# balancing_protection.net
KiCad netlist of a schematic drawn in Altium Designer
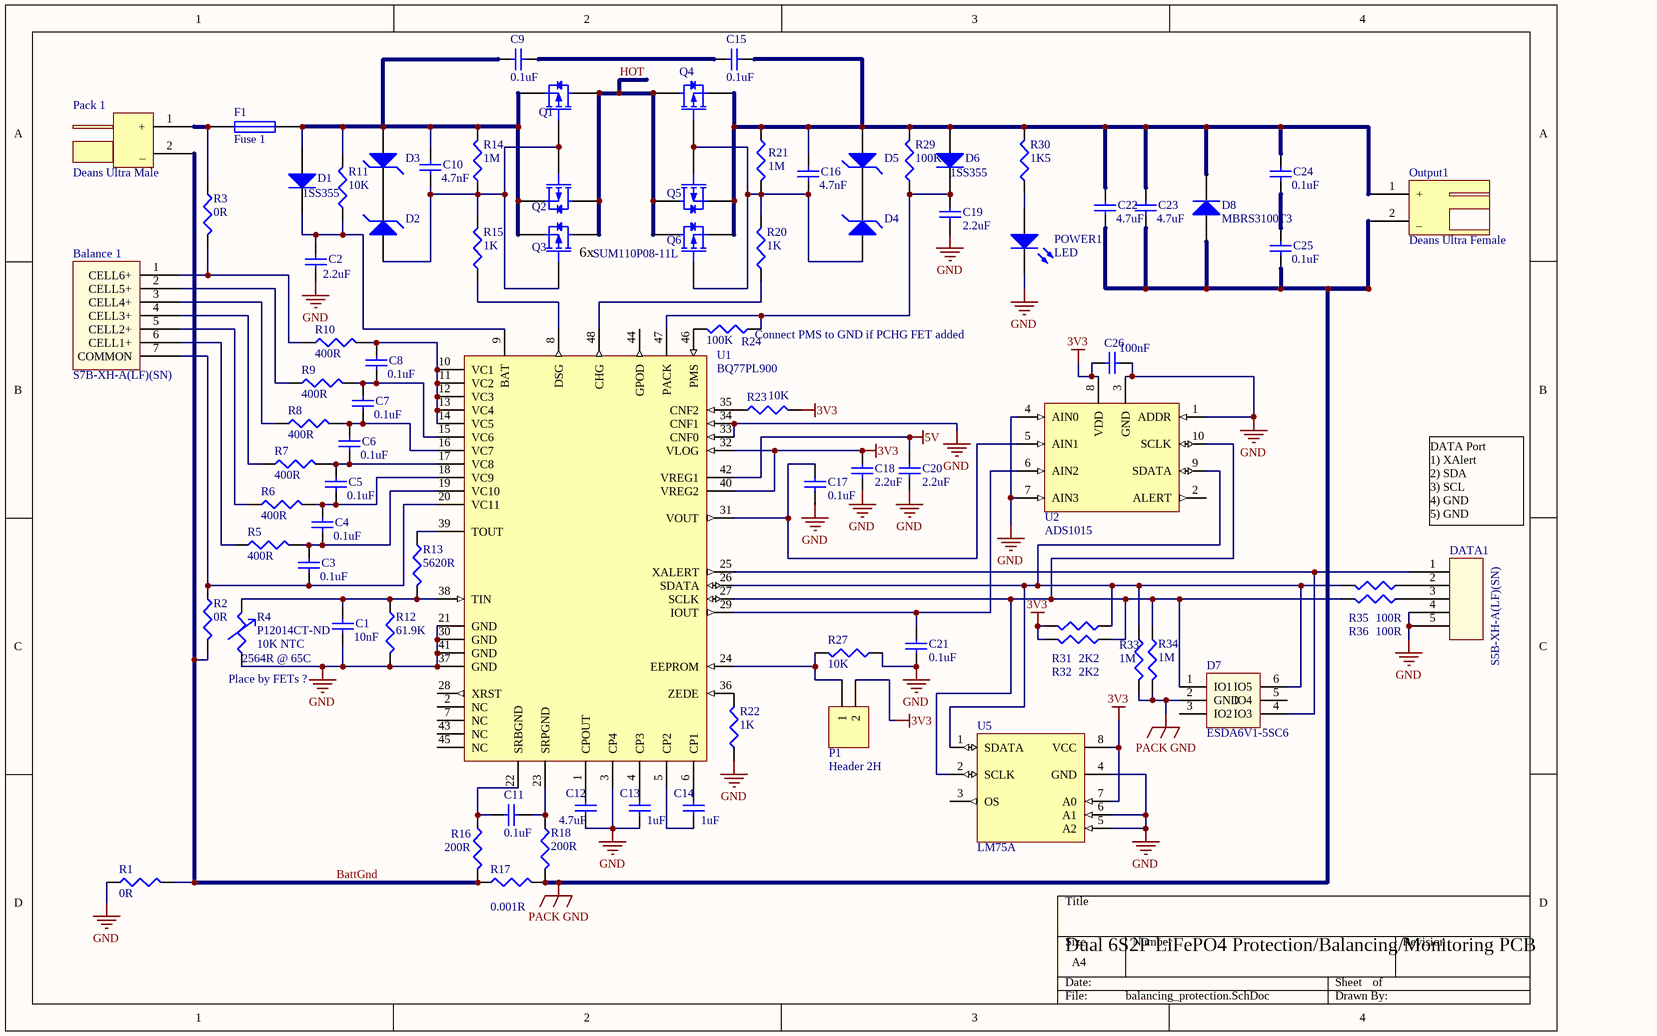
[diagram p0: balancing_protection.SchDoc]

(export (version "E")
  (design (tool "Eeschema 10.0.6"))
  (components
    (comp (ref "Balance 1")
      (value "S7B-XH-A(LF)(SN)")
      (footprint "XH_BALANCE_CONN")
      (description "Balancing Connector 455-2240-ND")
      (libsource (lib "parts") (part "S7B-XH-A(LF)(SN)"))
    )
    (comp (ref "C1")
      (value "10nF")
      (footprint "0603 - Hugo copy")
      (description "Capacitor (Semiconductor SIM Model)")
      (fields (field (name "Comment") "Cap Semi") (field (name "PUBLISHER") "Altium Limited"))
      (libsource (lib "Miscellaneous Devices") (part "Cap Semi"))
    )
    (comp (ref "C2")
      (value "2.2uF")
      (footprint "CAPC1206X06N")
      (description "TANTAMOUNT® 293D series tantalum 1206 cap")
      (fields (field (name "Comment") "718-1113-1-ND") (field (name "PUBLISHER") "Altium Limited"))
      (libsource (lib "parts") (part "TantCap1206"))
    )
    (comp (ref "C3")
      (value "0.1uF")
      (footprint "0603 - Hugo copy")
      (description "Capacitor (Semiconductor SIM Model)")
      (fields (field (name "Comment") "Cap Semi") (field (name "PUBLISHER") "Altium Limited"))
      (libsource (lib "Miscellaneous Devices") (part "Cap Semi"))
    )
    (comp (ref "C4")
      (value "0.1uF")
      (footprint "0603 - Hugo copy")
      (description "Capacitor (Semiconductor SIM Model)")
      (fields (field (name "Comment") "Cap Semi") (field (name "PUBLISHER") "Altium Limited"))
      (libsource (lib "Miscellaneous Devices") (part "Cap Semi"))
    )
    (comp (ref "C5")
      (value "0.1uF")
      (footprint "0603 - Hugo copy")
      (description "Capacitor (Semiconductor SIM Model)")
      (fields (field (name "Comment") "Cap Semi") (field (name "PUBLISHER") "Altium Limited"))
      (libsource (lib "Miscellaneous Devices") (part "Cap Semi"))
    )
    (comp (ref "C6")
      (value "0.1uF")
      (footprint "0603 - Hugo copy")
      (description "Capacitor (Semiconductor SIM Model)")
      (fields (field (name "Comment") "Cap Semi") (field (name "PUBLISHER") "Altium Limited"))
      (libsource (lib "Miscellaneous Devices") (part "Cap Semi"))
    )
    (comp (ref "C7")
      (value "0.1uF")
      (footprint "0603 - Hugo copy")
      (description "Capacitor (Semiconductor SIM Model)")
      (fields (field (name "Comment") "Cap Semi") (field (name "PUBLISHER") "Altium Limited"))
      (libsource (lib "Miscellaneous Devices") (part "Cap Semi"))
    )
    (comp (ref "C8")
      (value "0.1uF")
      (footprint "0603 - Hugo copy")
      (description "Capacitor (Semiconductor SIM Model)")
      (fields (field (name "Comment") "Cap Semi") (field (name "PUBLISHER") "Altium Limited"))
      (libsource (lib "Miscellaneous Devices") (part "Cap Semi"))
    )
    (comp (ref "C9")
      (value "0.1uF")
      (footprint "0603 - Hugo copy")
      (description "Capacitor (Semiconductor SIM Model)")
      (fields (field (name "Comment") "Cap Semi") (field (name "PUBLISHER") "Altium Limited"))
      (libsource (lib "Miscellaneous Devices") (part "Cap Semi"))
    )
    (comp (ref "C10")
      (value "4.7nF")
      (footprint "0603 - Hugo copy")
      (description "Capacitor (Semiconductor SIM Model)")
      (fields (field (name "Comment") "Cap Semi") (field (name "PUBLISHER") "Altium Limited"))
      (libsource (lib "Miscellaneous Devices") (part "Cap Semi"))
    )
    (comp (ref "C11")
      (value "0.1uF")
      (footprint "0603 - Hugo copy")
      (description "Capacitor (Semiconductor SIM Model)")
      (fields (field (name "Comment") "Cap Semi") (field (name "PUBLISHER") "Altium Limited"))
      (libsource (lib "Miscellaneous Devices") (part "Cap Semi"))
    )
    (comp (ref "C12")
      (value "4.7uF")
      (footprint "CAPC1210X10N")
      (description "TANTAMOUNT® 293D series tantalum 1206 cap")
      (fields (field (name "Comment") "718-1113-1-ND") (field (name "PUBLISHER") "Altium Limited"))
      (libsource (lib "parts") (part "TantCap1206"))
    )
    (comp (ref "C13")
      (value "1uF")
      (footprint "CAPC1206X06N")
      (description "TANTAMOUNT® 293D series tantalum 1206 cap")
      (fields (field (name "Comment") "718-1113-1-ND") (field (name "PUBLISHER") "Altium Limited"))
      (libsource (lib "parts") (part "TantCap1206"))
    )
    (comp (ref "C14")
      (value "1uF")
      (footprint "CAPC1206X06N")
      (description "TANTAMOUNT® 293D series tantalum 1206 cap")
      (fields (field (name "Comment") "718-1113-1-ND") (field (name "PUBLISHER") "Altium Limited"))
      (libsource (lib "parts") (part "TantCap1206"))
    )
    (comp (ref "C15")
      (value "0.1uF")
      (footprint "0603 - Hugo copy")
      (description "Capacitor (Semiconductor SIM Model)")
      (fields (field (name "Comment") "Cap Semi") (field (name "PUBLISHER") "Altium Limited"))
      (libsource (lib "Miscellaneous Devices") (part "Cap Semi"))
    )
    (comp (ref "C16")
      (value "4.7nF")
      (footprint "0603 - Hugo copy")
      (description "Capacitor (Semiconductor SIM Model)")
      (fields (field (name "Comment") "Cap Semi") (field (name "PUBLISHER") "Altium Limited"))
      (libsource (lib "Miscellaneous Devices") (part "Cap Semi"))
    )
    (comp (ref "C17")
      (value "0.1uF")
      (footprint "0603 - Hugo copy")
      (description "TANTAMOUNT® 293D series tantalum 1206 cap")
      (fields (field (name "Comment") "718-1113-1-ND") (field (name "PUBLISHER") "Altium Limited"))
      (libsource (lib "parts") (part "TantCap1206"))
    )
    (comp (ref "C18")
      (value "2.2uF")
      (footprint "0603 - Hugo copy")
      (description "TANTAMOUNT® 293D series tantalum 1206 cap")
      (fields (field (name "Comment") "718-1113-1-ND") (field (name "PUBLISHER") "Altium Limited"))
      (libsource (lib "parts") (part "TantCap1206"))
    )
    (comp (ref "C19")
      (value "2.2uF")
      (footprint "CAPC1206X06N")
      (description "TANTAMOUNT® 293D series tantalum 1206 cap")
      (fields (field (name "Comment") "718-1113-1-ND") (field (name "PUBLISHER") "Altium Limited"))
      (libsource (lib "parts") (part "TantCap1206"))
    )
    (comp (ref "C20")
      (value "2.2uF")
      (footprint "0603 - Hugo copy")
      (description "TANTAMOUNT® 293D series tantalum 1206 cap")
      (fields (field (name "Comment") "718-1113-1-ND") (field (name "PUBLISHER") "Altium Limited"))
      (libsource (lib "parts") (part "TantCap1206"))
    )
    (comp (ref "C21")
      (value "0.1uF")
      (footprint "0603 - Hugo copy")
      (description "TANTAMOUNT® 293D series tantalum 1206 cap")
      (fields (field (name "Comment") "718-1113-1-ND") (field (name "PUBLISHER") "Altium Limited"))
      (libsource (lib "parts") (part "TantCap1206"))
    )
    (comp (ref "C22")
      (value "4.7uF")
      (footprint "CAPC3216L")
      (description "Capacitor (Semiconductor SIM Model)")
      (fields (field (name "Comment") "Cap Semi") (field (name "PUBLISHER") "Altium Limited"))
      (libsource (lib "Miscellaneous Devices") (part "Cap Semi"))
    )
    (comp (ref "C23")
      (value "4.7uF")
      (footprint "CAPC3216L")
      (description "Capacitor (Semiconductor SIM Model)")
      (fields (field (name "Comment") "Cap Semi") (field (name "PUBLISHER") "Altium Limited"))
      (libsource (lib "Miscellaneous Devices") (part "Cap Semi"))
    )
    (comp (ref "C24")
      (value "0.1uF")
      (footprint "0603 - Hugo copy")
      (description "Capacitor (Semiconductor SIM Model)")
      (fields (field (name "Comment") "Cap Semi") (field (name "PUBLISHER") "Altium Limited"))
      (libsource (lib "Miscellaneous Devices") (part "Cap Semi"))
    )
    (comp (ref "C25")
      (value "0.1uF")
      (footprint "0603 - Hugo copy")
      (description "Capacitor (Semiconductor SIM Model)")
      (fields (field (name "Comment") "Cap Semi") (field (name "PUBLISHER") "Altium Limited"))
      (libsource (lib "Miscellaneous Devices") (part "Cap Semi"))
    )
    (comp (ref "C26")
      (value "100nF")
      (footprint "0603 - Hugo copy")
      (description "Capacitor (Semiconductor SIM Model)")
      (fields (field (name "Comment") "Cap Semi") (field (name "PUBLISHER") "Altium Limited"))
      (libsource (lib "Miscellaneous Devices") (part "Cap Semi"))
    )
    (comp (ref "D1")
      (value "1SS355")
      (footprint "SOD323-rough")
      (description "Diode, fast switch, 1SS355, 225mA")
      (fields (field (name "PUBLISHER") "Altium Limited"))
      (libsource (lib "parts") (part "1SS355"))
    )
    (comp (ref "D2")
      (value "BZX585-C16")
      (footprint "SOD523-rough")
      (description "DIODE ZENER 16V 300MW SOD523")
      (fields (field (name "PUBLISHER") "Altium Limited"))
      (libsource (lib "parts") (part "BZX585-C16"))
    )
    (comp (ref "D3")
      (value "BZX585-C16")
      (footprint "SOD523-rough")
      (description "DIODE ZENER 16V 300MW SOD523")
      (fields (field (name "PUBLISHER") "Altium Limited"))
      (libsource (lib "parts") (part "BZX585-C16"))
    )
    (comp (ref "D4")
      (value "BZX585-C16")
      (footprint "SOD523-rough")
      (description "DIODE ZENER 16V 300MW SOD523")
      (fields (field (name "PUBLISHER") "Altium Limited"))
      (libsource (lib "parts") (part "BZX585-C16"))
    )
    (comp (ref "D5")
      (value "BZX585-C16")
      (footprint "SOD523-rough")
      (description "DIODE ZENER 16V 300MW SOD523")
      (fields (field (name "PUBLISHER") "Altium Limited"))
      (libsource (lib "parts") (part "BZX585-C16"))
    )
    (comp (ref "D6")
      (value "1SS355")
      (footprint "SOD323-rough")
      (description "Diode, fast switch, 1SS355, 225mA")
      (fields (field (name "PUBLISHER") "Altium Limited"))
      (libsource (lib "parts") (part "1SS355"))
    )
    (comp (ref "D7")
      (value "ESDA6V1-5SC6")
      (footprint "SOT23-6")
      (description "5-signal ESD suppression TVS array")
      (fields (field (name "FARNELLPARTNUMBER") "1749270"))
      (libsource (lib "parts - hugo import") (part "TVS_ESDA6V1-5SC6"))
    )
    (comp (ref "D8")
      (value "MBRS3100T3")
      (footprint "SOJ300P790X241-2M-SMC Case 403")
      (description "Diode, schottky, 3A, 100V")
      (fields (field (name "PUBLISHER") "Altium Limited"))
      (libsource (lib "parts") (part "MBRS3100T3"))
    )
    (comp (ref "DATA1")
      (value "S5B-XH-A(LF)(SN)")
      (footprint "XH_I2C_CONN")
      (description "Balancing Connector 455-2242-ND")
      (libsource (lib "parts") (part "S5B-XH-A(LF)(SN)"))
    )
    (comp (ref "F1")
      (value "Fuse 1")
      (footprint "FUSE outline")
      (description "Keystone 3550-2 90 degree blade fuse holder")
      (fields (field (name "PUBLISHER") "Altium Limited"))
      (libsource (lib "Miscellaneous Devices") (part "Fuse 1"))
    )
    (comp (ref "Output1")
      (value "Deans Ultra Female")
      (footprint "DEANS_FEMALE_SIDEWAYS - n")
      (libsource (lib "parts") (part "DeansUltraFemale"))
    )
    (comp (ref "P1")
      (value "Header 2H")
      (footprint "HDR1X2H")
      (description "Header, 2-Pin, Right Angle")
      (fields (field (name "PUBLISHER") "Altium Limited"))
      (libsource (lib "Miscellaneous Connectors") (part "Header 2H"))
    )
    (comp (ref "Pack 1")
      (value "Deans Ultra Male")
      (footprint "DEANS_MALE_SIDEWAYS - n")
      (libsource (lib "parts") (part "DeansUltraMale"))
    )
    (comp (ref "POWER1")
      (value "LED")
      (footprint "parts:LED0805")
      (description "BLUE 0805 LED KP-2012MBC")
      (fields (field (name "PUBLISHER") "Altium Limited"))
      (libsource (lib "parts") (part "LED2"))
    )
    (comp (ref "Q1")
      (value "SUM110P08-11L")
      (footprint "D2PAK")
      (description "P-Channel MOSFET - SUM110P08-11L")
      (fields (field (name "PUBLISHER") "Altium Limited"))
      (libsource (lib "parts") (part "SUM110P08-11L"))
    )
    (comp (ref "Q2")
      (value "SUM110P08-11L")
      (footprint "D2PAK")
      (description "P-Channel MOSFET - SUM110P08-11L")
      (fields (field (name "PUBLISHER") "Altium Limited"))
      (libsource (lib "parts") (part "SUM110P08-11L"))
    )
    (comp (ref "Q3")
      (value "SUM110P08-11L")
      (footprint "D2PAK")
      (description "P-Channel MOSFET - SUM110P08-11L")
      (fields (field (name "PUBLISHER") "Altium Limited"))
      (libsource (lib "parts") (part "SUM110P08-11L"))
    )
    (comp (ref "Q4")
      (value "SUM110P08-11L")
      (footprint "D2PAK")
      (description "P-Channel MOSFET - SUM110P08-11L")
      (fields (field (name "PUBLISHER") "Altium Limited"))
      (libsource (lib "parts") (part "SUM110P08-11L"))
    )
    (comp (ref "Q5")
      (value "SUM110P08-11L")
      (footprint "D2PAK")
      (description "P-Channel MOSFET - SUM110P08-11L")
      (fields (field (name "PUBLISHER") "Altium Limited"))
      (libsource (lib "parts") (part "SUM110P08-11L"))
    )
    (comp (ref "Q6")
      (value "SUM110P08-11L")
      (footprint "D2PAK")
      (description "P-Channel MOSFET - SUM110P08-11L")
      (fields (field (name "PUBLISHER") "Altium Limited"))
      (libsource (lib "parts") (part "SUM110P08-11L"))
    )
    (comp (ref "R1")
      (value "0R")
      (footprint "0603 - Hugo copy")
      (description "Resistor 0R Ground Net Separation")
      (fields (field (name "Comment") "541-17.8ACCT-ND") (field (name "PUBLISHER") "Altium Limited"))
      (libsource (lib "parts") (part "541-17.8ACCT-ND"))
    )
    (comp (ref "R2")
      (value "0R")
      (footprint "0603 - Hugo Copy")
      (description "Resistor 0R Net Separation")
      (fields (field (name "Comment") "541-17.8ACCT-ND") (field (name "PUBLISHER") "Altium Limited"))
      (libsource (lib "parts") (part "541-17.8ACCT-ND"))
    )
    (comp (ref "R3")
      (value "0R")
      (footprint "0603 - Hugo Copy")
      (description "Resistor 0R Net Separation")
      (fields (field (name "Comment") "541-17.8ACCT-ND") (field (name "PUBLISHER") "Altium Limited"))
      (libsource (lib "parts") (part "541-17.8ACCT-ND"))
    )
    (comp (ref "R4")
      (value "P12014CT-ND")
      (footprint "0603 - Hugo copy")
      (description "10k NTC Thermistor 0603")
      (fields (field (name "ALTIUM_VALUE") "10K NTC") (field (name "PUBLISHER") "Altium Limited"))
      (libsource (lib "parts") (part "P12014CT-ND"))
    )
    (comp (ref "R5")
      (value "400R")
      (footprint "0603 - HUGO COPY")
      (description "Resistor 400R Balancing")
      (fields (field (name "Comment") "541-17.8ACCT-ND") (field (name "PUBLISHER") "Altium Limited"))
      (libsource (lib "parts") (part "541-17.8ACCT-ND"))
    )
    (comp (ref "R6")
      (value "400R")
      (footprint "0603 - HUGO COPY")
      (description "Resistor 400R Balancing")
      (fields (field (name "Comment") "541-17.8ACCT-ND") (field (name "PUBLISHER") "Altium Limited"))
      (libsource (lib "parts") (part "541-17.8ACCT-ND"))
    )
    (comp (ref "R7")
      (value "400R")
      (footprint "0603 - HUGO COPY")
      (description "Resistor 400R Balancing")
      (fields (field (name "Comment") "541-17.8ACCT-ND") (field (name "PUBLISHER") "Altium Limited"))
      (libsource (lib "parts") (part "541-17.8ACCT-ND"))
    )
    (comp (ref "R8")
      (value "400R")
      (footprint "0603 - HUGO COPY")
      (description "Resistor 400R Balancing")
      (fields (field (name "Comment") "541-17.8ACCT-ND") (field (name "PUBLISHER") "Altium Limited"))
      (libsource (lib "parts") (part "541-17.8ACCT-ND"))
    )
    (comp (ref "R9")
      (value "400R")
      (footprint "0603 - HUGO COPY")
      (description "Resistor 400R Balancing")
      (fields (field (name "Comment") "541-17.8ACCT-ND") (field (name "PUBLISHER") "Altium Limited"))
      (libsource (lib "parts") (part "541-17.8ACCT-ND"))
    )
    (comp (ref "R10")
      (value "400R")
      (footprint "0603 - HUGO COPY")
      (description "Resistor 400R Balancing")
      (fields (field (name "Comment") "541-17.8ACCT-ND") (field (name "PUBLISHER") "Altium Limited"))
      (libsource (lib "parts") (part "541-17.8ACCT-ND"))
    )
    (comp (ref "R11")
      (value "10K")
      (footprint "0603 - HUGO COPY")
      (description "Resistor 10K C11 discharge (short circuit)")
      (fields (field (name "Comment") "541-17.8ACCT-ND") (field (name "PUBLISHER") "Altium Limited"))
      (libsource (lib "parts") (part "541-17.8ACCT-ND"))
    )
    (comp (ref "R12")
      (value "61.9K")
      (footprint "0603 - HUGO COPY")
      (description "Resistor 61.9K Linearisation")
      (fields (field (name "Comment") "541-17.8ACCT-ND") (field (name "PUBLISHER") "Altium Limited"))
      (libsource (lib "parts") (part "541-17.8ACCT-ND"))
    )
    (comp (ref "R13")
      (value "5620R")
      (footprint "0603 - HUGO COPY")
      (description "Resistor 5620R Thermistor potential divider")
      (fields (field (name "Comment") "541-17.8ACCT-ND") (field (name "PUBLISHER") "Altium Limited"))
      (libsource (lib "parts") (part "541-17.8ACCT-ND"))
    )
    (comp (ref "R14")
      (value "1M")
      (footprint "0603 - HUGO COPY")
      (description "Resistor 1M FET gate protection?")
      (fields (field (name "Comment") "Res3") (field (name "PUBLISHER") "Altium Limited"))
      (libsource (lib "Miscellaneous Devices") (part "Res3"))
    )
    (comp (ref "R15")
      (value "1K")
      (footprint "0603 - HUGO COPY")
      (description "Resistor 1K FET Gate drive resistor")
      (fields (field (name "Comment") "Res3") (field (name "PUBLISHER") "Altium Limited"))
      (libsource (lib "Miscellaneous Devices") (part "Res3"))
    )
    (comp (ref "R16")
      (value "200R")
      (footprint "0603 - HUGO COPY")
      (description "Resistor 200R sense time const")
      (fields (field (name "Comment") "541-17.8ACCT-ND") (field (name "PUBLISHER") "Altium Limited"))
      (libsource (lib "parts") (part "541-17.8ACCT-ND"))
    )
    (comp (ref "R17")
      (value "0.001R")
      (footprint "RESC2512")
      (description "Resistor 0.001R Sense")
      (fields (field (name "Comment") "PR2512FKG7W0R001L") (field (name "PUBLISHER") "Altium Limited"))
      (libsource (lib "parts") (part "MCS3264R005FERCT-ND"))
    )
    (comp (ref "R18")
      (value "200R")
      (footprint "0603 - HUGO COPY")
      (description "Resistor 200R sense time const")
      (fields (field (name "Comment") "541-17.8ACCT-ND") (field (name "PUBLISHER") "Altium Limited"))
      (libsource (lib "parts") (part "541-17.8ACCT-ND"))
    )
    (comp (ref "R20")
      (value "1K")
      (footprint "0603 - HUGO COPY")
      (description "Resistor 1K FET Gate drive resistor")
      (fields (field (name "Comment") "Res3") (field (name "PUBLISHER") "Altium Limited"))
      (libsource (lib "Miscellaneous Devices") (part "Res3"))
    )
    (comp (ref "R21")
      (value "1M")
      (footprint "0603 - HUGO COPY")
      (description "Resistor 1M FET gate protection?")
      (fields (field (name "Comment") "Res3") (field (name "PUBLISHER") "Altium Limited"))
      (libsource (lib "Miscellaneous Devices") (part "Res3"))
    )
    (comp (ref "R22")
      (value "1K")
      (footprint "0603 - HUGO COPY")
      (description "Resistor 1K Pull Down")
      (fields (field (name "Comment") "541-17.8ACCT-ND") (field (name "PUBLISHER") "Altium Limited"))
      (libsource (lib "parts") (part "541-17.8ACCT-ND"))
    )
    (comp (ref "R23")
      (value "10K")
      (footprint "0603 - HUGO COPY")
      (description "Resistor 10K Pull up")
      (fields (field (name "Comment") "541-17.8ACCT-ND") (field (name "PUBLISHER") "Altium Limited"))
      (libsource (lib "parts") (part "541-17.8ACCT-ND"))
    )
    (comp (ref "R24")
      (value "100K")
      (footprint "0603 - HUGO COPY")
      (description "Resistor 100K Pre-charge mode select")
      (fields (field (name "Comment") "541-17.8ACCT-ND") (field (name "PUBLISHER") "Altium Limited"))
      (libsource (lib "parts") (part "541-17.8ACCT-ND"))
    )
    (comp (ref "R27")
      (value "10K")
      (footprint "0603 - HUGO COPY")
      (description "Resistor 10K Pull up/down")
      (fields (field (name "Comment") "541-17.8ACCT-ND") (field (name "PUBLISHER") "Altium Limited"))
      (libsource (lib "parts") (part "541-17.8ACCT-ND"))
    )
    (comp (ref "R29")
      (value "100K")
      (footprint "0603 - HUGO COPY")
      (description "Resistor 100K C19 discharge (short circuit)")
      (fields (field (name "Comment") "541-17.8ACCT-ND") (field (name "PUBLISHER") "Altium Limited"))
      (libsource (lib "parts") (part "541-17.8ACCT-ND"))
    )
    (comp (ref "R30")
      (value "1K5")
      (footprint "0603 - Hugo copy")
      (description "Resistor 2.5K LED current limit CRCW06031K50FKEAHP")
      (fields (field (name "Comment") "Res3") (field (name "PUBLISHER") "Altium Limited"))
      (libsource (lib "Miscellaneous Devices") (part "Res3"))
    )
    (comp (ref "R31")
      (value "2K2")
      (footprint "0603 - HUGO COPY")
      (description "Resistor 4K7 I2C  pul-up")
      (fields (field (name "Comment") "Res3") (field (name "PUBLISHER") "Altium Limited"))
      (libsource (lib "Miscellaneous Devices") (part "Res3"))
    )
    (comp (ref "R32")
      (value "2K2")
      (footprint "0603 - HUGO COPY")
      (description "Resistor 4K7 I2C  pul-up")
      (fields (field (name "Comment") "Res3") (field (name "PUBLISHER") "Altium Limited"))
      (libsource (lib "Miscellaneous Devices") (part "Res3"))
    )
    (comp (ref "R33")
      (value "1M")
      (footprint "0603 - HUGO COPY")
      (description "Resistor 1M I2C pull down or protection?")
      (fields (field (name "Comment") "541-17.8ACCT-ND") (field (name "PUBLISHER") "Altium Limited"))
      (libsource (lib "parts") (part "541-17.8ACCT-ND"))
    )
    (comp (ref "R34")
      (value "1M")
      (footprint "0603 - HUGO COPY")
      (description "Resistor 17.8R Balancing")
      (fields (field (name "Comment") "541-17.8ACCT-ND") (field (name "PUBLISHER") "Altium Limited"))
      (libsource (lib "parts") (part "541-17.8ACCT-ND"))
    )
    (comp (ref "R35")
      (value "100R")
      (footprint "0603 - HUGO COPY")
      (description "Resistor 100R I2C  protection")
      (fields (field (name "Comment") "Res3") (field (name "PUBLISHER") "Altium Limited"))
      (libsource (lib "Miscellaneous Devices") (part "Res3"))
    )
    (comp (ref "R36")
      (value "100R")
      (footprint "0603 - HUGO COPY")
      (description "Resistor 100R I2C  protection")
      (fields (field (name "Comment") "Res3") (field (name "PUBLISHER") "Altium Limited"))
      (libsource (lib "Miscellaneous Devices") (part "Res3"))
    )
    (comp (ref "U1")
      (value "BQ77PL900")
      (footprint "SOP63P1030X279-48N")
      (description "Battery protector/AFE")
      (libsource (lib "parts") (part "BQ77PL900"))
    )
    (comp (ref "U2")
      (value "ADS1015")
      (footprint "TSSOP50P490X110-10N")
      (description "Quad I/P I2C ADC")
      (libsource (lib "parts") (part "ADS1015"))
    )
    (comp (ref "U5")
      (value "LM75A")
      (footprint "SOP127P600X175-8N")
      (description "Digital temperature sensor and thermal watchdog")
      (libsource (lib "parts") (part "LM75A"))
    )
  )
  (nets
    (net (code "1") (name "/BattGnd") (class "Default")
      (node (ref "Pack 1") (pin "2") (pinfunction "__2") (pintype "power_in"))
      (node (ref "R1") (pin "2") (pinfunction "2_2") (pintype "passive"))
      (node (ref "R16") (pin "2") (pinfunction "2_2") (pintype "passive"))
      (node (ref "R17") (pin "1") (pinfunction "1_1") (pintype "passive"))
      (node (ref "R2") (pin "2") (pinfunction "2_2") (pintype "passive"))
    )
    (net (code "2") (name "/HOT") (class "Default")
      (node (ref "Q1") (pin "1") (pinfunction "D_1") (pintype "passive"))
      (node (ref "Q2") (pin "1") (pinfunction "D_1") (pintype "passive"))
      (node (ref "Q3") (pin "1") (pinfunction "D_1") (pintype "passive"))
      (node (ref "Q4") (pin "1") (pinfunction "D_1") (pintype "passive"))
      (node (ref "Q5") (pin "1") (pinfunction "D_1") (pintype "passive"))
      (node (ref "Q6") (pin "1") (pinfunction "D_1") (pintype "passive"))
    )
    (net (code "3") (name "3V3") (class "Default")
      (node (ref "C18") (pin "2") (pinfunction "2_2") (pintype "passive"))
      (node (ref "C26") (pin "2") (pinfunction "2_2") (pintype "passive"))
      (node (ref "P1") (pin "2") (pinfunction "2_2") (pintype "passive"))
      (node (ref "R23") (pin "2") (pinfunction "2_2") (pintype "passive"))
      (node (ref "R31") (pin "2") (pinfunction "2_2") (pintype "passive"))
      (node (ref "R32") (pin "2") (pinfunction "2_2") (pintype "passive"))
      (node (ref "U1") (pin "32") (pinfunction "VLOG_32") (pintype "input"))
      (node (ref "U1") (pin "40") (pinfunction "VREG2_40") (pintype "power_in"))
      (node (ref "U2") (pin "8") (pinfunction "VDD_8") (pintype "power_in"))
      (node (ref "U5") (pin "7") (pinfunction "A0_7") (pintype "input"))
      (node (ref "U5") (pin "8") (pinfunction "VCC_8") (pintype "power_in"))
    )
    (net (code "4") (name "5V") (class "Default")
      (node (ref "C20") (pin "2") (pinfunction "2_2") (pintype "passive"))
      (node (ref "U1") (pin "42") (pinfunction "VREG1_42") (pintype "power_in"))
    )
    (net (code "5") (name "GND") (class "Default")
      (node (ref "C1") (pin "1") (pinfunction "1_1") (pintype "passive"))
      (node (ref "C12") (pin "2") (pinfunction "2_2") (pintype "passive"))
      (node (ref "C13") (pin "2") (pinfunction "2_2") (pintype "passive"))
      (node (ref "C17") (pin "2") (pinfunction "2_2") (pintype "passive"))
      (node (ref "C18") (pin "1") (pinfunction "1_1") (pintype "passive"))
      (node (ref "C19") (pin "1") (pinfunction "1_1") (pintype "passive"))
      (node (ref "C2") (pin "1") (pinfunction "1_1") (pintype "passive"))
      (node (ref "C20") (pin "1") (pinfunction "1_1") (pintype "passive"))
      (node (ref "C21") (pin "1") (pinfunction "1_1") (pintype "passive"))
      (node (ref "C26") (pin "1") (pinfunction "1_1") (pintype "passive"))
      (node (ref "DATA1") (pin "4") (pintype "passive"))
      (node (ref "DATA1") (pin "5") (pintype "passive"))
      (node (ref "POWER1") (pin "2") (pinfunction "K_2") (pintype "passive"))
      (node (ref "R1") (pin "1") (pinfunction "1_1") (pintype "passive"))
      (node (ref "R12") (pin "2") (pinfunction "2_2") (pintype "passive"))
      (node (ref "R22") (pin "1") (pinfunction "1_1") (pintype "passive"))
      (node (ref "R27") (pin "1") (pinfunction "1_1") (pintype "passive"))
      (node (ref "R4") (pin "1") (pinfunction "1_1") (pintype "passive"))
      (node (ref "U1") (pin "21") (pinfunction "GND_21") (pintype "passive"))
      (node (ref "U1") (pin "3") (pinfunction "CP4_3") (pintype "passive"))
      (node (ref "U1") (pin "30") (pinfunction "GND_30") (pintype "power_in"))
      (node (ref "U1") (pin "33") (pinfunction "CNF0_33") (pintype "input"))
      (node (ref "U1") (pin "34") (pinfunction "CNF1_34") (pintype "input"))
      (node (ref "U1") (pin "37") (pinfunction "GND_37") (pintype "power_in"))
      (node (ref "U1") (pin "41") (pinfunction "GND_41") (pintype "power_in"))
      (node (ref "U2") (pin "1") (pinfunction "ADDR_1") (pintype "input"))
      (node (ref "U2") (pin "3") (pinfunction "GND_3") (pintype "power_in"))
      (node (ref "U2") (pin "4") (pinfunction "AIN0_4") (pintype "input"))
      (node (ref "U2") (pin "7") (pinfunction "AIN3_7") (pintype "input"))
      (node (ref "U5") (pin "4") (pinfunction "GND_4") (pintype "power_in"))
      (node (ref "U5") (pin "5") (pinfunction "A2_5") (pintype "input"))
      (node (ref "U5") (pin "6") (pinfunction "A1_6") (pintype "input"))
    )
    (net (code "6") (name "Net-(Balance 1-CELL1+)") (class "Default")
      (node (ref "Balance 1") (pin "6") (pinfunction "CELL1+_6") (pintype "power_in"))
      (node (ref "R5") (pin "1") (pinfunction "1_1") (pintype "passive"))
    )
    (net (code "7") (name "Net-(Balance 1-CELL2+)") (class "Default")
      (node (ref "Balance 1") (pin "5") (pinfunction "CELL2+_5") (pintype "power_in"))
      (node (ref "R6") (pin "1") (pinfunction "1_1") (pintype "passive"))
    )
    (net (code "8") (name "Net-(Balance 1-CELL3+)") (class "Default")
      (node (ref "Balance 1") (pin "4") (pinfunction "CELL3+_4") (pintype "power_in"))
      (node (ref "R7") (pin "1") (pinfunction "1_1") (pintype "passive"))
    )
    (net (code "9") (name "Net-(Balance 1-CELL4+)") (class "Default")
      (node (ref "Balance 1") (pin "3") (pinfunction "CELL4+_3") (pintype "power_in"))
      (node (ref "R8") (pin "1") (pinfunction "1_1") (pintype "passive"))
    )
    (net (code "10") (name "Net-(Balance 1-CELL5+)") (class "Default")
      (node (ref "Balance 1") (pin "2") (pinfunction "CELL5+_2") (pintype "power_in"))
      (node (ref "R9") (pin "1") (pinfunction "1_1") (pintype "passive"))
    )
    (net (code "11") (name "Net-(Balance 1-CELL6+)") (class "Default")
      (node (ref "Balance 1") (pin "1") (pinfunction "CELL6+_1") (pintype "power_in"))
      (node (ref "R10") (pin "1") (pinfunction "1_1") (pintype "passive"))
      (node (ref "R3") (pin "2") (pinfunction "2_2") (pintype "passive"))
    )
    (net (code "12") (name "Net-(Balance 1-COMMON)") (class "Default")
      (node (ref "Balance 1") (pin "7") (pinfunction "COMMON_7") (pintype "power_in"))
      (node (ref "C3") (pin "1") (pinfunction "1_1") (pintype "passive"))
      (node (ref "R2") (pin "1") (pinfunction "1_1") (pintype "passive"))
      (node (ref "U1") (pin "20") (pinfunction "VC11_20") (pintype "passive"))
    )
    (net (code "13") (name "Net-(C15-Pad2)") (class "Default")
      (node (ref "C15") (pin "2") (pinfunction "2_2") (pintype "passive"))
      (node (ref "C9") (pin "1") (pinfunction "1_1") (pintype "passive"))
    )
    (net (code "14") (name "Net-(C24-Pad1)") (class "Default")
      (node (ref "C24") (pin "1") (pinfunction "1_1") (pintype "passive"))
      (node (ref "C25") (pin "2") (pinfunction "2_2") (pintype "passive"))
    )
    (net (code "15") (name "Net-(D1-A)") (class "Default")
      (node (ref "C10") (pin "2") (pinfunction "2_2") (pintype "passive"))
      (node (ref "C9") (pin "2") (pinfunction "2_2") (pintype "passive"))
      (node (ref "D1") (pin "1") (pinfunction "A_1") (pintype "passive"))
      (node (ref "D3") (pin "2") (pinfunction "A_2") (pintype "passive"))
      (node (ref "F1") (pin "1") (pinfunction "1_1") (pintype "passive"))
      (node (ref "Q1") (pin "3") (pinfunction "S_3") (pintype "passive"))
      (node (ref "Q2") (pin "3") (pinfunction "S_3") (pintype "passive"))
      (node (ref "Q3") (pin "3") (pinfunction "S_3") (pintype "passive"))
      (node (ref "R11") (pin "2") (pinfunction "2_2") (pintype "passive"))
      (node (ref "R14") (pin "2") (pinfunction "2_2") (pintype "passive"))
    )
    (net (code "16") (name "Net-(D1-K)") (class "Default")
      (node (ref "C2") (pin "2") (pinfunction "2_2") (pintype "passive"))
      (node (ref "D1") (pin "2") (pinfunction "K_2") (pintype "passive"))
      (node (ref "R11") (pin "1") (pinfunction "1_1") (pintype "passive"))
      (node (ref "U1") (pin "9") (pinfunction "BAT_9") (pintype "power_in"))
    )
    (net (code "17") (name "Net-(D2-A)") (class "Default")
      (node (ref "C10") (pin "1") (pinfunction "1_1") (pintype "passive"))
      (node (ref "D2") (pin "2") (pinfunction "A_2") (pintype "passive"))
      (node (ref "Q1") (pin "2") (pinfunction "G_2") (pintype "passive"))
      (node (ref "Q2") (pin "2") (pinfunction "G_2") (pintype "passive"))
      (node (ref "Q3") (pin "2") (pinfunction "G_2") (pintype "passive"))
      (node (ref "R14") (pin "1") (pinfunction "1_1") (pintype "passive"))
      (node (ref "R15") (pin "2") (pinfunction "2_2") (pintype "passive"))
    )
    (net (code "18") (name "Net-(D2-K)") (class "Default")
      (node (ref "D2") (pin "1") (pinfunction "K_1") (pintype "passive"))
      (node (ref "D3") (pin "1") (pinfunction "K_1") (pintype "passive"))
    )
    (net (code "19") (name "Net-(D4-A)") (class "Default")
      (node (ref "C16") (pin "1") (pinfunction "1_1") (pintype "passive"))
      (node (ref "D4") (pin "2") (pinfunction "A_2") (pintype "passive"))
      (node (ref "Q4") (pin "2") (pinfunction "G_2") (pintype "passive"))
      (node (ref "Q5") (pin "2") (pinfunction "G_2") (pintype "passive"))
      (node (ref "Q6") (pin "2") (pinfunction "G_2") (pintype "passive"))
      (node (ref "R20") (pin "2") (pinfunction "2_2") (pintype "passive"))
      (node (ref "R21") (pin "2") (pinfunction "2_2") (pintype "passive"))
    )
    (net (code "20") (name "Net-(D4-K)") (class "Default")
      (node (ref "D4") (pin "1") (pinfunction "K_1") (pintype "passive"))
      (node (ref "D5") (pin "1") (pinfunction "K_1") (pintype "passive"))
    )
    (net (code "21") (name "Net-(D5-A)") (class "Default")
      (node (ref "C15") (pin "1") (pinfunction "1_1") (pintype "passive"))
      (node (ref "C16") (pin "2") (pinfunction "2_2") (pintype "passive"))
      (node (ref "C22") (pin "2") (pinfunction "2_2") (pintype "passive"))
      (node (ref "C23") (pin "2") (pinfunction "2_2") (pintype "passive"))
      (node (ref "C24") (pin "2") (pinfunction "2_2") (pintype "passive"))
      (node (ref "D5") (pin "2") (pinfunction "A_2") (pintype "passive"))
      (node (ref "D6") (pin "1") (pinfunction "A_1") (pintype "passive"))
      (node (ref "D8") (pin "2") (pinfunction "K_2") (pintype "passive"))
      (node (ref "Output1") (pin "1") (pinfunction "+_1") (pintype "power_in"))
      (node (ref "Q4") (pin "3") (pinfunction "S_3") (pintype "passive"))
      (node (ref "Q5") (pin "3") (pinfunction "S_3") (pintype "passive"))
      (node (ref "Q6") (pin "3") (pinfunction "S_3") (pintype "passive"))
      (node (ref "R21") (pin "1") (pinfunction "1_1") (pintype "passive"))
      (node (ref "R29") (pin "2") (pinfunction "2_2") (pintype "passive"))
      (node (ref "R30") (pin "2") (pinfunction "2_2") (pintype "passive"))
    )
    (net (code "22") (name "Net-(D6-K)") (class "Default")
      (node (ref "C19") (pin "2") (pinfunction "2_2") (pintype "passive"))
      (node (ref "D6") (pin "2") (pinfunction "K_2") (pintype "passive"))
      (node (ref "R24") (pin "1") (pinfunction "1_1") (pintype "passive"))
      (node (ref "R29") (pin "1") (pinfunction "1_1") (pintype "passive"))
      (node (ref "U1") (pin "47") (pinfunction "PACK_47") (pintype "power_in"))
    )
    (net (code "23") (name "Net-(D7-IO1)") (class "Default")
      (node (ref "D7") (pin "1") (pinfunction "IO1_1") (pintype "passive"))
      (node (ref "R32") (pin "1") (pinfunction "1_1") (pintype "passive"))
      (node (ref "R34") (pin "1") (pinfunction "1_1") (pintype "passive"))
      (node (ref "R36") (pin "2") (pinfunction "2_2") (pintype "passive"))
      (node (ref "U1") (pin "27") (pinfunction "SCLK_27") (pintype "bidirectional"))
      (node (ref "U2") (pin "10") (pinfunction "SCLK_10") (pintype "bidirectional"))
      (node (ref "U5") (pin "2") (pinfunction "SCLK_2") (pintype "bidirectional"))
    )
    (net (code "24") (name "Net-(D7-IO3)") (class "Default")
      (node (ref "D7") (pin "4") (pinfunction "IO3_4") (pintype "passive"))
      (node (ref "DATA1") (pin "1") (pintype "passive"))
      (node (ref "U1") (pin "25") (pinfunction "XALERT_25") (pintype "output"))
    )
    (net (code "25") (name "Net-(D7-IO5)") (class "Default")
      (node (ref "D7") (pin "6") (pinfunction "IO5_6") (pintype "passive"))
      (node (ref "R31") (pin "1") (pinfunction "1_1") (pintype "passive"))
      (node (ref "R33") (pin "1") (pinfunction "1_1") (pintype "passive"))
      (node (ref "R35") (pin "2") (pinfunction "2_2") (pintype "passive"))
      (node (ref "U1") (pin "26") (pinfunction "SDATA_26") (pintype "bidirectional"))
      (node (ref "U2") (pin "9") (pinfunction "SDATA_9") (pintype "bidirectional"))
      (node (ref "U5") (pin "1") (pinfunction "SDATA_1") (pintype "bidirectional"))
    )
    (net (code "26") (name "Net-(DATA1-Pad2)") (class "Default")
      (node (ref "DATA1") (pin "2") (pintype "passive"))
      (node (ref "R35") (pin "1") (pinfunction "1_1") (pintype "passive"))
    )
    (net (code "27") (name "Net-(DATA1-Pad3)") (class "Default")
      (node (ref "DATA1") (pin "3") (pintype "passive"))
      (node (ref "R36") (pin "1") (pinfunction "1_1") (pintype "passive"))
    )
    (net (code "28") (name "Net-(POWER1-A)") (class "Default")
      (node (ref "POWER1") (pin "1") (pinfunction "A_1") (pintype "passive"))
      (node (ref "R30") (pin "1") (pinfunction "1_1") (pintype "passive"))
    )
    (net (code "29") (name "Net-(Pack 1-+)") (class "Default")
      (node (ref "F1") (pin "2") (pinfunction "2_2") (pintype "passive"))
      (node (ref "Pack 1") (pin "1") (pinfunction "+_1") (pintype "power_in"))
      (node (ref "R3") (pin "1") (pinfunction "1_1") (pintype "passive"))
    )
    (net (code "30") (name "Net-(U1-CHG)") (class "Default")
      (node (ref "R20") (pin "1") (pinfunction "1_1") (pintype "passive"))
      (node (ref "U1") (pin "48") (pinfunction "CHG_48") (pintype "output"))
    )
    (net (code "31") (name "Net-(U1-CNF2)") (class "Default")
      (node (ref "R23") (pin "1") (pinfunction "1_1") (pintype "passive"))
      (node (ref "U1") (pin "35") (pinfunction "CNF2_35") (pintype "input"))
    )
    (net (code "32") (name "Net-(U1-CP1)") (class "Default")
      (node (ref "C14") (pin "1") (pinfunction "1_1") (pintype "passive"))
      (node (ref "U1") (pin "6") (pinfunction "CP1_6") (pintype "passive"))
    )
    (net (code "33") (name "Net-(U1-CP2)") (class "Default")
      (node (ref "C14") (pin "2") (pinfunction "2_2") (pintype "passive"))
      (node (ref "U1") (pin "5") (pinfunction "CP2_5") (pintype "passive"))
    )
    (net (code "34") (name "Net-(U1-CP3)") (class "Default")
      (node (ref "C13") (pin "1") (pinfunction "1_1") (pintype "passive"))
      (node (ref "U1") (pin "4") (pinfunction "CP3_4") (pintype "passive"))
    )
    (net (code "35") (name "Net-(U1-CPOUT)") (class "Default")
      (node (ref "C12") (pin "1") (pinfunction "1_1") (pintype "passive"))
      (node (ref "U1") (pin "1") (pinfunction "CPOUT_1") (pintype "passive"))
    )
    (net (code "36") (name "Net-(U1-DSG)") (class "Default")
      (node (ref "R15") (pin "1") (pinfunction "1_1") (pintype "passive"))
      (node (ref "U1") (pin "8") (pinfunction "DSG_8") (pintype "output"))
    )
    (net (code "37") (name "Net-(U1-EEPROM)") (class "Default")
      (node (ref "P1") (pin "1") (pinfunction "1_1") (pintype "passive"))
      (node (ref "R27") (pin "2") (pinfunction "2_2") (pintype "passive"))
      (node (ref "U1") (pin "24") (pinfunction "EEPROM_24") (pintype "input"))
    )
    (net (code "38") (name "Net-(U1-IOUT)") (class "Default")
      (node (ref "C21") (pin "2") (pinfunction "2_2") (pintype "passive"))
      (node (ref "U1") (pin "29") (pinfunction "IOUT_29") (pintype "output"))
      (node (ref "U2") (pin "6") (pinfunction "AIN2_6") (pintype "input"))
    )
    (net (code "39") (name "Net-(U1-PMS)") (class "Default")
      (node (ref "R24") (pin "2") (pinfunction "2_2") (pintype "passive"))
      (node (ref "U1") (pin "46") (pinfunction "PMS_46") (pintype "input"))
    )
    (net (code "40") (name "Net-(U1-SRBGND)") (class "Default")
      (node (ref "C11") (pin "1") (pinfunction "1_1") (pintype "passive"))
      (node (ref "R16") (pin "1") (pinfunction "1_1") (pintype "passive"))
      (node (ref "U1") (pin "22") (pinfunction "SRBGND_22") (pintype "passive"))
    )
    (net (code "41") (name "Net-(U1-SRPGND)") (class "Default")
      (node (ref "C11") (pin "2") (pinfunction "2_2") (pintype "passive"))
      (node (ref "R18") (pin "1") (pinfunction "1_1") (pintype "passive"))
      (node (ref "U1") (pin "23") (pinfunction "SRPGND_23") (pintype "passive"))
    )
    (net (code "42") (name "Net-(U1-TIN)") (class "Default")
      (node (ref "C1") (pin "2") (pinfunction "2_2") (pintype "passive"))
      (node (ref "R12") (pin "1") (pinfunction "1_1") (pintype "passive"))
      (node (ref "R13") (pin "2") (pinfunction "2_2") (pintype "passive"))
      (node (ref "R4") (pin "2") (pinfunction "2_2") (pintype "passive"))
      (node (ref "U1") (pin "38") (pinfunction "TIN_38") (pintype "input"))
    )
    (net (code "43") (name "Net-(U1-TOUT)") (class "Default")
      (node (ref "R13") (pin "1") (pinfunction "1_1") (pintype "passive"))
      (node (ref "U1") (pin "39") (pinfunction "TOUT_39") (pintype "passive"))
    )
    (net (code "44") (name "Net-(U1-VC1)") (class "Default")
      (node (ref "C8") (pin "2") (pinfunction "2_2") (pintype "passive"))
      (node (ref "R10") (pin "2") (pinfunction "2_2") (pintype "passive"))
      (node (ref "U1") (pin "10") (pinfunction "VC1_10") (pintype "passive"))
      (node (ref "U1") (pin "11") (pinfunction "VC2_11") (pintype "passive"))
      (node (ref "U1") (pin "12") (pinfunction "VC3_12") (pintype "passive"))
      (node (ref "U1") (pin "13") (pinfunction "VC4_13") (pintype "passive"))
      (node (ref "U1") (pin "14") (pinfunction "VC5_14") (pintype "passive"))
    )
    (net (code "45") (name "Net-(U1-VC6)") (class "Default")
      (node (ref "C7") (pin "2") (pinfunction "2_2") (pintype "passive"))
      (node (ref "C8") (pin "1") (pinfunction "1_1") (pintype "passive"))
      (node (ref "R9") (pin "2") (pinfunction "2_2") (pintype "passive"))
      (node (ref "U1") (pin "15") (pinfunction "VC6_15") (pintype "passive"))
    )
    (net (code "46") (name "Net-(U1-VC7)") (class "Default")
      (node (ref "C6") (pin "2") (pinfunction "2_2") (pintype "passive"))
      (node (ref "C7") (pin "1") (pinfunction "1_1") (pintype "passive"))
      (node (ref "R8") (pin "2") (pinfunction "2_2") (pintype "passive"))
      (node (ref "U1") (pin "16") (pinfunction "VC7_16") (pintype "passive"))
    )
    (net (code "47") (name "Net-(U1-VC8)") (class "Default")
      (node (ref "C5") (pin "2") (pinfunction "2_2") (pintype "passive"))
      (node (ref "C6") (pin "1") (pinfunction "1_1") (pintype "passive"))
      (node (ref "R7") (pin "2") (pinfunction "2_2") (pintype "passive"))
      (node (ref "U1") (pin "17") (pinfunction "VC8_17") (pintype "passive"))
    )
    (net (code "48") (name "Net-(U1-VC9)") (class "Default")
      (node (ref "C4") (pin "2") (pinfunction "2_2") (pintype "passive"))
      (node (ref "C5") (pin "1") (pinfunction "1_1") (pintype "passive"))
      (node (ref "R6") (pin "2") (pinfunction "2_2") (pintype "passive"))
      (node (ref "U1") (pin "18") (pinfunction "VC9_18") (pintype "passive"))
    )
    (net (code "49") (name "Net-(U1-VC10)") (class "Default")
      (node (ref "C3") (pin "2") (pinfunction "2_2") (pintype "passive"))
      (node (ref "C4") (pin "1") (pinfunction "1_1") (pintype "passive"))
      (node (ref "R5") (pin "2") (pinfunction "2_2") (pintype "passive"))
      (node (ref "U1") (pin "19") (pinfunction "VC10_19") (pintype "passive"))
    )
    (net (code "50") (name "Net-(U1-VOUT)") (class "Default")
      (node (ref "C17") (pin "1") (pinfunction "1_1") (pintype "passive"))
      (node (ref "U1") (pin "31") (pinfunction "VOUT_31") (pintype "output"))
      (node (ref "U2") (pin "5") (pinfunction "AIN1_5") (pintype "input"))
    )
    (net (code "51") (name "Net-(U1-ZEDE)") (class "Default")
      (node (ref "R22") (pin "2") (pinfunction "2_2") (pintype "passive"))
      (node (ref "U1") (pin "36") (pinfunction "ZEDE_36") (pintype "input"))
    )
    (net (code "52") (name "PACK GND") (class "Default")
      (node (ref "C22") (pin "1") (pinfunction "1_1") (pintype "passive"))
      (node (ref "C23") (pin "1") (pinfunction "1_1") (pintype "passive"))
      (node (ref "C25") (pin "1") (pinfunction "1_1") (pintype "passive"))
      (node (ref "D7") (pin "2") (pinfunction "GND_2") (pintype "passive"))
      (node (ref "D8") (pin "1") (pinfunction "A_1") (pintype "passive"))
      (node (ref "Output1") (pin "2") (pinfunction "__2") (pintype "power_in"))
      (node (ref "R17") (pin "2") (pinfunction "2_2") (pintype "passive"))
      (node (ref "R18") (pin "2") (pinfunction "2_2") (pintype "passive"))
      (node (ref "R33") (pin "2") (pinfunction "2_2") (pintype "passive"))
      (node (ref "R34") (pin "2") (pinfunction "2_2") (pintype "passive"))
    )
    (net (code "53") (name "unconnected-(D7-IO2-Pad3)") (class "Default")
      (node (ref "D7") (pin "3") (pinfunction "IO2_3") (pintype "passive"))
    )
    (net (code "54") (name "unconnected-(D7-IO4-Pad5)") (class "Default")
      (node (ref "D7") (pin "5") (pinfunction "IO4_5") (pintype "passive"))
    )
    (net (code "55") (name "unconnected-(U1-GPOD-Pad44)") (class "Default")
      (node (ref "U1") (pin "44") (pinfunction "GPOD_44") (pintype "output"))
    )
    (net (code "56") (name "unconnected-(U1-NC-Pad2)") (class "Default")
      (node (ref "U1") (pin "2") (pinfunction "NC_2") (pintype "passive"))
    )
    (net (code "57") (name "unconnected-(U1-NC-Pad7)") (class "Default")
      (node (ref "U1") (pin "7") (pinfunction "NC_7") (pintype "passive"))
    )
    (net (code "58") (name "unconnected-(U1-NC-Pad43)") (class "Default")
      (node (ref "U1") (pin "43") (pinfunction "NC_43") (pintype "passive"))
    )
    (net (code "59") (name "unconnected-(U1-NC-Pad45)") (class "Default")
      (node (ref "U1") (pin "45") (pinfunction "NC_45") (pintype "passive"))
    )
    (net (code "60") (name "unconnected-(U1-XRST-Pad28)") (class "Default")
      (node (ref "U1") (pin "28") (pinfunction "XRST_28") (pintype "output"))
    )
    (net (code "61") (name "unconnected-(U2-ALERT-Pad2)") (class "Default")
      (node (ref "U2") (pin "2") (pinfunction "ALERT_2") (pintype "output"))
    )
    (net (code "62") (name "unconnected-(U5-OS-Pad3)") (class "Default")
      (node (ref "U5") (pin "3") (pinfunction "OS_3") (pintype "output"))
    )
  )
)
